# Modem_Carrier.net
KiCad netlist of a schematic drawn in EasyEDA Pro
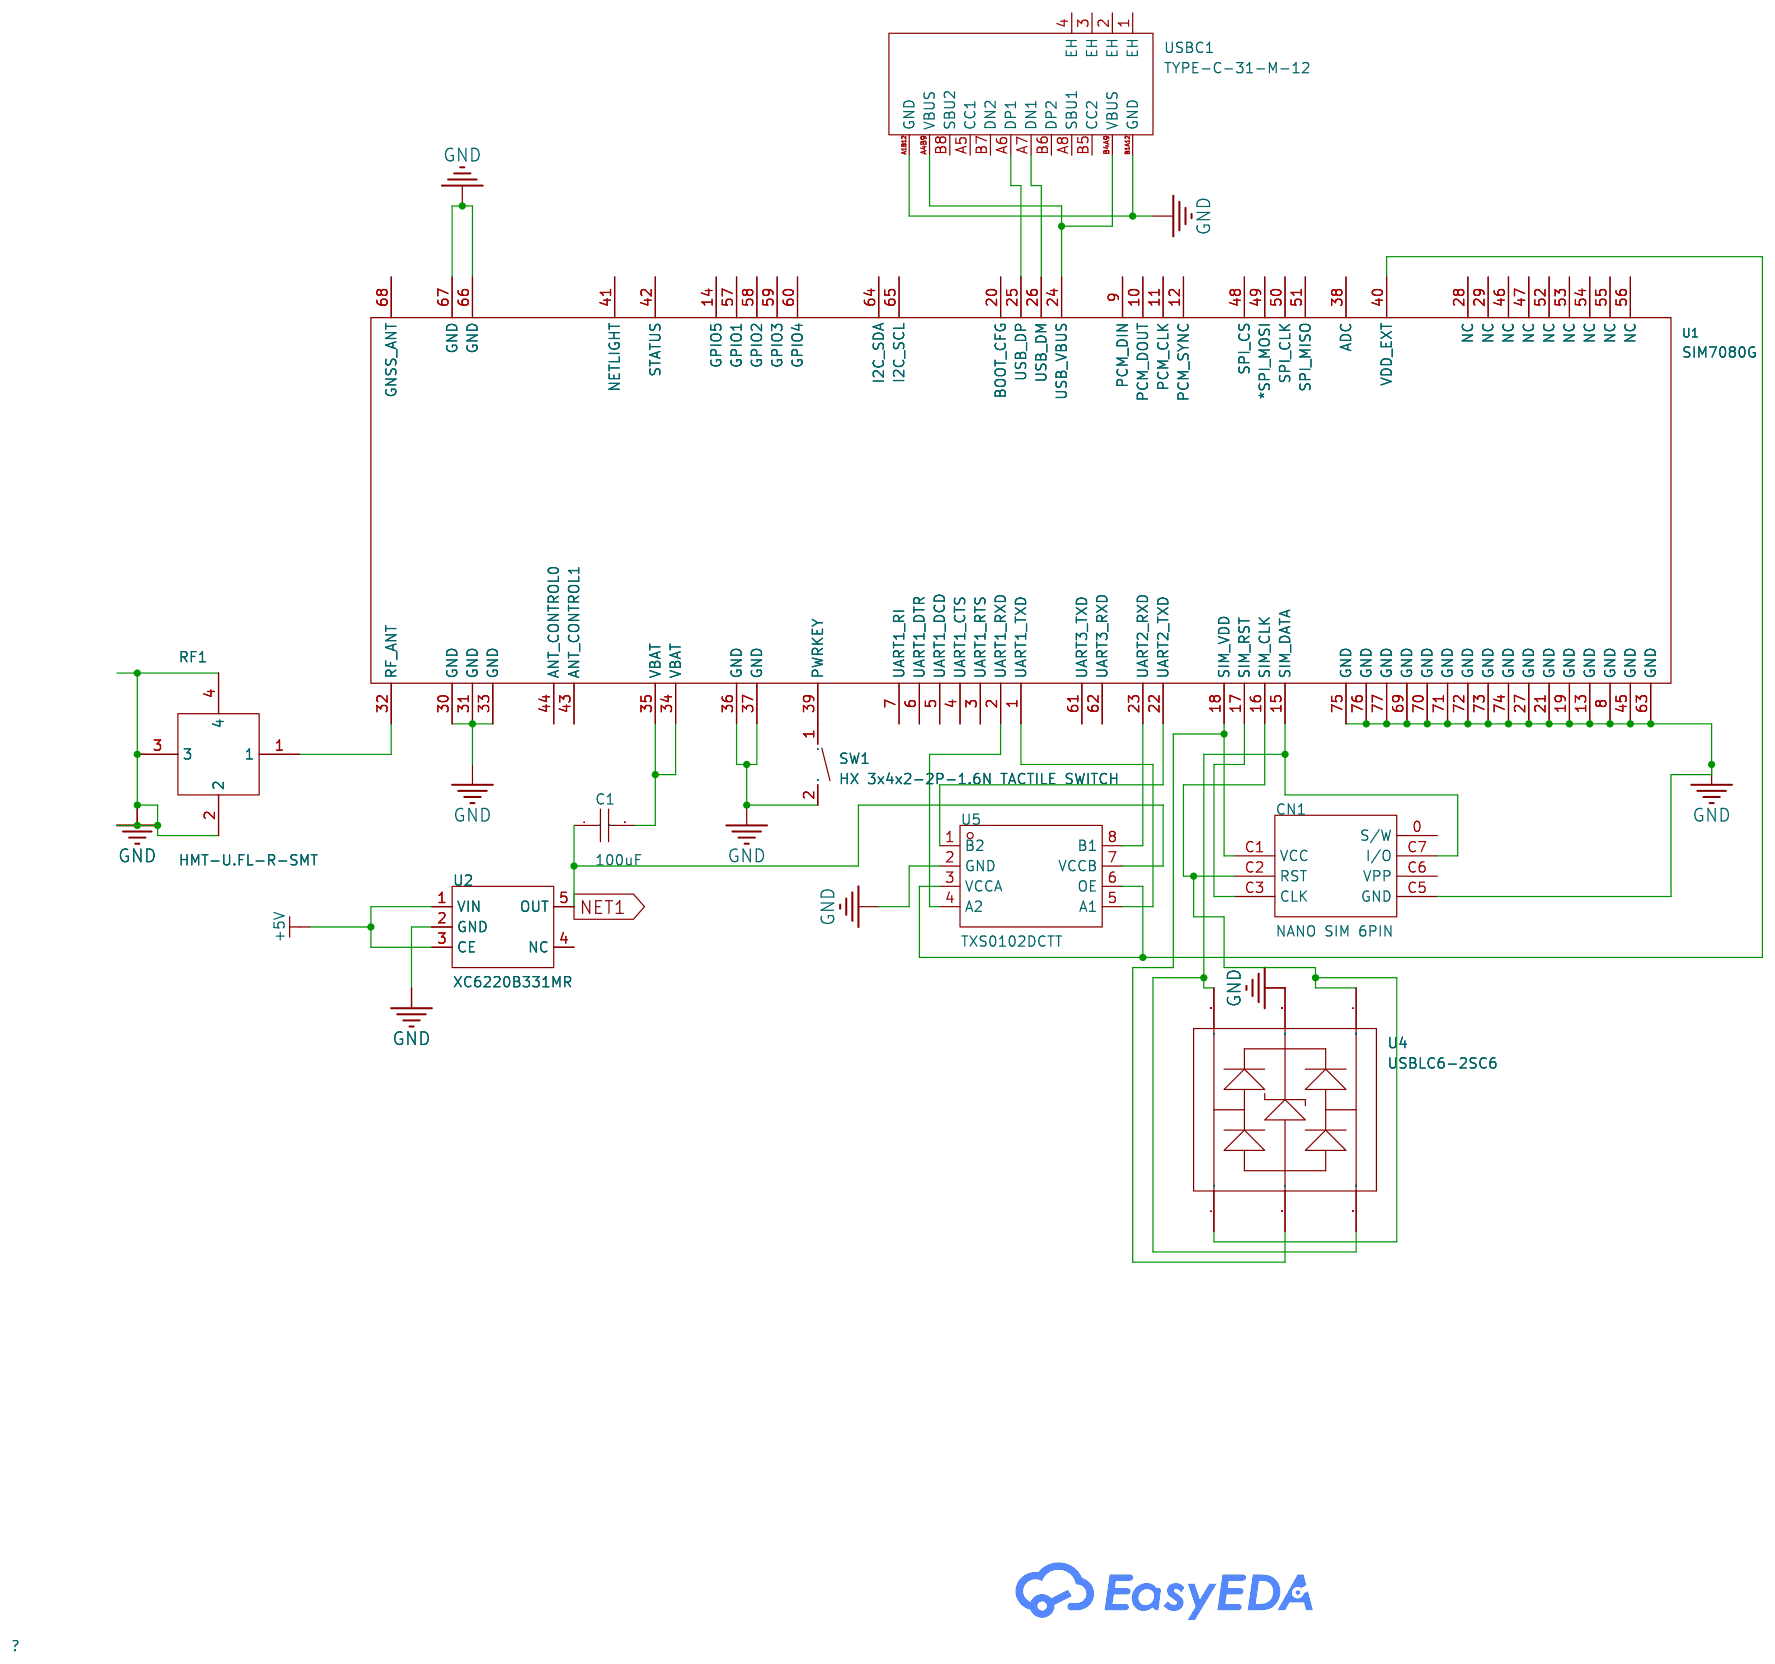
[diagram p0: schematic sheet]

(export (version "E")
  (design (tool "Eeschema 10.0.6"))
  (components
    (comp (ref "C1")
      (value "100uF")
      (footprint "easyedapro:C1206")
      (description "Capacitance:100uF Tolerance:±20% Tolerance:±20% Voltage Rating:6.3V Temperature Coefficient:X5R")
      (fields
        (field (name "Manufacturer Part") "CL31A107MQHNNNE")
        (field (name "Manufacturer") "SAMSUNG(三星)")
      )
      (libsource (lib "easyedapro") (part "CL31A107MQHNNNE"))
    )
    (comp (ref "CN1")
      (value "NANO SIM 6PIN")
      (footprint "easyedapro:SIM-SMD_C77877")
      (fields (field (name "Manufacturer") "BOOMELE(博穆精密)"))
      (libsource (lib "easyedapro") (part "nano1.4_c77877"))
    )
    (comp (ref "RF1")
      (value "HMT-U.FL-R-SMT")
      (footprint "easyedapro:IPEX-SMD_4P-L2.6-W2.6-LS3.1")
      (fields (field (name "Manufacturer") "HMTCONN(华明通)"))
      (libsource (lib "easyedapro") (part "HMT-U.FL-R-SMT"))
    )
    (comp (ref "SW1")
      (value "HX 3x4x2-2P-1.6N TACTILE SWITCH")
      (footprint "easyedapro:KEY-SMD_L4.0-W3.0-LS4.9-1")
      (fields (field (name "Manufacturer") "hanxia(韩下)"))
      (libsource (lib "easyedapro") (part "HX 3X4X2-2P-1.6N TACTILE SWITCH"))
    )
    (comp (ref "U1")
      (value "SIM7080G")
      (footprint "easyedapro:LCC-SMD_SIM7080G")
      (fields (field (name "Manufacturer") "SIMCOM(芯讯通无线科技)"))
      (libsource (lib "easyedapro") (part "SIM7080G"))
    )
    (comp (ref "U2")
      (value "XC6220B331MR")
      (footprint "easyedapro:SOT-23-5_L2.9-W1.6-P0.95-LS2.8-BR")
      (fields (field (name "Manufacturer") "TECH PUBLIC(台舟)"))
      (libsource (lib "easyedapro") (part "XC6220B331MR"))
    )
    (comp (ref "U4")
      (value "USBLC6-2SC6")
      (footprint "easyedapro:SOT-23-6_L2.9-W1.6-P0.95-LS2.8-BL")
      (fields (field (name "Manufacturer") "FUXINSEMI(富芯森美)"))
      (libsource (lib "easyedapro") (part "USBLC6-2SC6_C6807798"))
    )
    (comp (ref "U5")
      (value "TXS0102DCTT")
      (footprint "easyedapro:SSOP-8_L3.0-W2.8-P0.65-LS4.0-BL")
      (fields (field (name "Manufacturer") "TI(德州仪器)"))
      (libsource (lib "easyedapro") (part "TXS0102DCTT"))
    )
    (comp (ref "USBC1")
      (value "TYPE-C-31-M-12")
      (footprint "easyedapro:USB-C_SMD-TYPE-C-31-M-12_1")
      (fields (field (name "Manufacturer") "韩国韩荣"))
      (libsource (lib "easyedapro") (part "TYPE-C-31-M-12"))
    )
  )
  (nets
    (net (code "1") (name "+5V") (class "Default")
      (node (ref "U2") (pin "1") (pinfunction "VIN_1") (pintype "unspecified"))
      (node (ref "U2") (pin "3") (pinfunction "CE_3") (pintype "unspecified"))
    )
    (net (code "2") (name "GND") (class "Default")
      (node (ref "CN1") (pin "C5") (pinfunction "GND_C5") (pintype "unspecified"))
      (node (ref "RF1") (pin "2") (pinfunction "2_2") (pintype "unspecified"))
      (node (ref "RF1") (pin "3") (pinfunction "3_3") (pintype "unspecified"))
      (node (ref "RF1") (pin "4") (pinfunction "4_4") (pintype "unspecified"))
      (node (ref "SW1") (pin "2") (pinfunction "2_2") (pintype "unspecified"))
      (node (ref "U1") (pin "13") (pinfunction "GND_13") (pintype "input"))
      (node (ref "U1") (pin "19") (pinfunction "GND_19") (pintype "input"))
      (node (ref "U1") (pin "21") (pinfunction "GND_21") (pintype "input"))
      (node (ref "U1") (pin "27") (pinfunction "GND_27") (pintype "input"))
      (node (ref "U1") (pin "30") (pinfunction "GND_30") (pintype "input"))
      (node (ref "U1") (pin "31") (pinfunction "GND_31") (pintype "input"))
      (node (ref "U1") (pin "33") (pinfunction "GND_33") (pintype "input"))
      (node (ref "U1") (pin "36") (pinfunction "GND_36") (pintype "input"))
      (node (ref "U1") (pin "37") (pinfunction "GND_37") (pintype "input"))
      (node (ref "U1") (pin "45") (pinfunction "GND_45") (pintype "input"))
      (node (ref "U1") (pin "63") (pinfunction "GND_63") (pintype "input"))
      (node (ref "U1") (pin "66") (pinfunction "GND_66") (pintype "input"))
      (node (ref "U1") (pin "67") (pinfunction "GND_67") (pintype "input"))
      (node (ref "U1") (pin "69") (pinfunction "GND_69") (pintype "input"))
      (node (ref "U1") (pin "70") (pinfunction "GND_70") (pintype "input"))
      (node (ref "U1") (pin "71") (pinfunction "GND_71") (pintype "input"))
      (node (ref "U1") (pin "72") (pinfunction "GND_72") (pintype "input"))
      (node (ref "U1") (pin "73") (pinfunction "GND_73") (pintype "input"))
      (node (ref "U1") (pin "74") (pinfunction "GND_74") (pintype "input"))
      (node (ref "U1") (pin "75") (pinfunction "GND_75") (pintype "input"))
      (node (ref "U1") (pin "76") (pinfunction "GND_76") (pintype "input"))
      (node (ref "U1") (pin "77") (pinfunction "GND_77") (pintype "input"))
      (node (ref "U1") (pin "8") (pinfunction "GND_8") (pintype "input"))
      (node (ref "U2") (pin "2") (pinfunction "GND_2") (pintype "unspecified"))
      (node (ref "U4") (pin "5") (pinfunction "VCC_5") (pintype "input"))
      (node (ref "U5") (pin "2") (pinfunction "GND_2") (pintype "unspecified"))
      (node (ref "USBC1") (pin "A1B12") (pinfunction "GND_A1B12") (pintype "unspecified"))
      (node (ref "USBC1") (pin "B1A12") (pinfunction "GND_B1A12") (pintype "unspecified"))
    )
    (net (code "3") (name "NET1") (class "Default")
      (node (ref "C1") (pin "1") (pinfunction "1_1") (pintype "input"))
      (node (ref "U2") (pin "5") (pinfunction "OUT_5") (pintype "unspecified"))
      (node (ref "U5") (pin "7") (pinfunction "VCCB_7") (pintype "unspecified"))
    )
    (net (code "4") (name "Net-(C1-Pad2)") (class "Default")
      (node (ref "C1") (pin "2") (pinfunction "2_2") (pintype "input"))
      (node (ref "U1") (pin "34") (pinfunction "VBAT_34") (pintype "input"))
      (node (ref "U1") (pin "35") (pinfunction "VBAT_35") (pintype "input"))
    )
    (net (code "5") (name "Net-(CN1-CLK)") (class "Default")
      (node (ref "CN1") (pin "C3") (pinfunction "CLK_C3") (pintype "unspecified"))
      (node (ref "U1") (pin "17") (pinfunction "SIM_RST_17") (pintype "input"))
    )
    (net (code "6") (name "Net-(CN1-I{slash}O)") (class "Default")
      (node (ref "CN1") (pin "C7") (pinfunction "I/O_C7") (pintype "unspecified"))
      (node (ref "U1") (pin "15") (pinfunction "SIM_DATA_15") (pintype "input"))
      (node (ref "U4") (pin "3") (pinfunction "I/O2_3") (pintype "input"))
      (node (ref "U4") (pin "6") (pinfunction "I/O1_6") (pintype "input"))
    )
    (net (code "7") (name "Net-(CN1-RST)") (class "Default")
      (node (ref "CN1") (pin "C2") (pinfunction "RST_C2") (pintype "unspecified"))
      (node (ref "U1") (pin "16") (pinfunction "SIM_CLK_16") (pintype "input"))
      (node (ref "U4") (pin "1") (pinfunction "I/O1_1") (pintype "input"))
      (node (ref "U4") (pin "4") (pinfunction "I/O2_4") (pintype "input"))
    )
    (net (code "8") (name "Net-(CN1-VCC)") (class "Default")
      (node (ref "CN1") (pin "C1") (pinfunction "VCC_C1") (pintype "unspecified"))
      (node (ref "U1") (pin "18") (pinfunction "SIM_VDD_18") (pintype "input"))
      (node (ref "U4") (pin "2") (pinfunction "GND_2") (pintype "input"))
    )
    (net (code "9") (name "Net-(U1-PWRKEY)") (class "Default")
      (node (ref "SW1") (pin "1") (pinfunction "1_1") (pintype "unspecified"))
      (node (ref "U1") (pin "39") (pinfunction "PWRKEY_39") (pintype "input"))
    )
    (net (code "10") (name "Net-(U1-RF_ANT)") (class "Default")
      (node (ref "RF1") (pin "1") (pinfunction "1_1") (pintype "unspecified"))
      (node (ref "U1") (pin "32") (pinfunction "RF_ANT_32") (pintype "input"))
    )
    (net (code "11") (name "Net-(U1-UART1_RXD)") (class "Default")
      (node (ref "U1") (pin "2") (pinfunction "UART1_RXD_2") (pintype "input"))
      (node (ref "U5") (pin "4") (pinfunction "A2_4") (pintype "unspecified"))
    )
    (net (code "12") (name "Net-(U1-UART1_TXD)") (class "Default")
      (node (ref "U1") (pin "1") (pinfunction "UART1_TXD_1") (pintype "input"))
      (node (ref "U5") (pin "5") (pinfunction "A1_5") (pintype "unspecified"))
    )
    (net (code "13") (name "Net-(U1-UART2_RXD)") (class "Default")
      (node (ref "U1") (pin "23") (pinfunction "UART2_RXD_23") (pintype "input"))
      (node (ref "U5") (pin "8") (pinfunction "B1_8") (pintype "unspecified"))
    )
    (net (code "14") (name "Net-(U1-UART2_TXD)") (class "Default")
      (node (ref "U1") (pin "22") (pinfunction "UART2_TXD_22") (pintype "input"))
      (node (ref "U5") (pin "1") (pinfunction "B2_1") (pintype "unspecified"))
    )
    (net (code "15") (name "Net-(U1-USB_DM)") (class "Default")
      (node (ref "U1") (pin "26") (pinfunction "USB_DM_26") (pintype "input"))
      (node (ref "USBC1") (pin "A7") (pinfunction "DN1_A7") (pintype "unspecified"))
    )
    (net (code "16") (name "Net-(U1-USB_DP)") (class "Default")
      (node (ref "U1") (pin "25") (pinfunction "USB_DP_25") (pintype "input"))
      (node (ref "USBC1") (pin "A6") (pinfunction "DP1_A6") (pintype "unspecified"))
    )
    (net (code "17") (name "Net-(U1-USB_VBUS)") (class "Default")
      (node (ref "U1") (pin "24") (pinfunction "USB_VBUS_24") (pintype "input"))
      (node (ref "USBC1") (pin "A4B9") (pinfunction "VBUS_A4B9") (pintype "unspecified"))
      (node (ref "USBC1") (pin "B4A9") (pinfunction "VBUS_B4A9") (pintype "unspecified"))
    )
    (net (code "18") (name "Net-(U1-VDD_EXT)") (class "Default")
      (node (ref "U1") (pin "40") (pinfunction "VDD_EXT_40") (pintype "input"))
      (node (ref "U5") (pin "3") (pinfunction "VCCA_3") (pintype "unspecified"))
      (node (ref "U5") (pin "6") (pinfunction "OE_6") (pintype "unspecified"))
    )
    (net (code "19") (name "unconnected-(CN1-S{slash}W-Pad0)") (class "Default")
      (node (ref "CN1") (pin "0") (pinfunction "S/W_0") (pintype "unspecified"))
    )
    (net (code "20") (name "unconnected-(CN1-VPP-PadC6)") (class "Default")
      (node (ref "CN1") (pin "C6") (pinfunction "VPP_C6") (pintype "unspecified"))
    )
    (net (code "21") (name "unconnected-(U1-*SPI_MOSI-Pad49)") (class "Default")
      (node (ref "U1") (pin "49") (pinfunction "*SPI_MOSI_49") (pintype "input"))
    )
    (net (code "22") (name "unconnected-(U1-ADC-Pad38)") (class "Default")
      (node (ref "U1") (pin "38") (pinfunction "ADC_38") (pintype "input"))
    )
    (net (code "23") (name "unconnected-(U1-ANT_CONTROL0-Pad44)") (class "Default")
      (node (ref "U1") (pin "44") (pinfunction "ANT_CONTROL0_44") (pintype "input"))
    )
    (net (code "24") (name "unconnected-(U1-ANT_CONTROL1-Pad43)") (class "Default")
      (node (ref "U1") (pin "43") (pinfunction "ANT_CONTROL1_43") (pintype "input"))
    )
    (net (code "25") (name "unconnected-(U1-BOOT_CFG-Pad20)") (class "Default")
      (node (ref "U1") (pin "20") (pinfunction "BOOT_CFG_20") (pintype "input"))
    )
    (net (code "26") (name "unconnected-(U1-GNSS_ANT-Pad68)") (class "Default")
      (node (ref "U1") (pin "68") (pinfunction "GNSS_ANT_68") (pintype "input"))
    )
    (net (code "27") (name "unconnected-(U1-GPIO1-Pad57)") (class "Default")
      (node (ref "U1") (pin "57") (pinfunction "GPIO1_57") (pintype "input"))
    )
    (net (code "28") (name "unconnected-(U1-GPIO2-Pad58)") (class "Default")
      (node (ref "U1") (pin "58") (pinfunction "GPIO2_58") (pintype "input"))
    )
    (net (code "29") (name "unconnected-(U1-GPIO3-Pad59)") (class "Default")
      (node (ref "U1") (pin "59") (pinfunction "GPIO3_59") (pintype "input"))
    )
    (net (code "30") (name "unconnected-(U1-GPIO4-Pad60)") (class "Default")
      (node (ref "U1") (pin "60") (pinfunction "GPIO4_60") (pintype "input"))
    )
    (net (code "31") (name "unconnected-(U1-GPIO5-Pad14)") (class "Default")
      (node (ref "U1") (pin "14") (pinfunction "GPIO5_14") (pintype "input"))
    )
    (net (code "32") (name "unconnected-(U1-I2C_SCL-Pad65)") (class "Default")
      (node (ref "U1") (pin "65") (pinfunction "I2C_SCL_65") (pintype "input"))
    )
    (net (code "33") (name "unconnected-(U1-I2C_SDA-Pad64)") (class "Default")
      (node (ref "U1") (pin "64") (pinfunction "I2C_SDA_64") (pintype "input"))
    )
    (net (code "34") (name "unconnected-(U1-NC-Pad28)") (class "Default")
      (node (ref "U1") (pin "28") (pinfunction "NC_28") (pintype "input"))
    )
    (net (code "35") (name "unconnected-(U1-NC-Pad29)") (class "Default")
      (node (ref "U1") (pin "29") (pinfunction "NC_29") (pintype "input"))
    )
    (net (code "36") (name "unconnected-(U1-NC-Pad46)") (class "Default")
      (node (ref "U1") (pin "46") (pinfunction "NC_46") (pintype "input"))
    )
    (net (code "37") (name "unconnected-(U1-NC-Pad47)") (class "Default")
      (node (ref "U1") (pin "47") (pinfunction "NC_47") (pintype "input"))
    )
    (net (code "38") (name "unconnected-(U1-NC-Pad52)") (class "Default")
      (node (ref "U1") (pin "52") (pinfunction "NC_52") (pintype "input"))
    )
    (net (code "39") (name "unconnected-(U1-NC-Pad53)") (class "Default")
      (node (ref "U1") (pin "53") (pinfunction "NC_53") (pintype "input"))
    )
    (net (code "40") (name "unconnected-(U1-NC-Pad54)") (class "Default")
      (node (ref "U1") (pin "54") (pinfunction "NC_54") (pintype "input"))
    )
    (net (code "41") (name "unconnected-(U1-NC-Pad55)") (class "Default")
      (node (ref "U1") (pin "55") (pinfunction "NC_55") (pintype "input"))
    )
    (net (code "42") (name "unconnected-(U1-NC-Pad56)") (class "Default")
      (node (ref "U1") (pin "56") (pinfunction "NC_56") (pintype "input"))
    )
    (net (code "43") (name "unconnected-(U1-NETLIGHT-Pad41)") (class "Default")
      (node (ref "U1") (pin "41") (pinfunction "NETLIGHT_41") (pintype "input"))
    )
    (net (code "44") (name "unconnected-(U1-PCM_CLK-Pad11)") (class "Default")
      (node (ref "U1") (pin "11") (pinfunction "PCM_CLK_11") (pintype "input"))
    )
    (net (code "45") (name "unconnected-(U1-PCM_DIN-Pad9)") (class "Default")
      (node (ref "U1") (pin "9") (pinfunction "PCM_DIN_9") (pintype "input"))
    )
    (net (code "46") (name "unconnected-(U1-PCM_DOUT-Pad10)") (class "Default")
      (node (ref "U1") (pin "10") (pinfunction "PCM_DOUT_10") (pintype "input"))
    )
    (net (code "47") (name "unconnected-(U1-PCM_SYNC-Pad12)") (class "Default")
      (node (ref "U1") (pin "12") (pinfunction "PCM_SYNC_12") (pintype "input"))
    )
    (net (code "48") (name "unconnected-(U1-SPI_CLK-Pad50)") (class "Default")
      (node (ref "U1") (pin "50") (pinfunction "SPI_CLK_50") (pintype "input"))
    )
    (net (code "49") (name "unconnected-(U1-SPI_CS-Pad48)") (class "Default")
      (node (ref "U1") (pin "48") (pinfunction "SPI_CS_48") (pintype "input"))
    )
    (net (code "50") (name "unconnected-(U1-SPI_MISO-Pad51)") (class "Default")
      (node (ref "U1") (pin "51") (pinfunction "SPI_MISO_51") (pintype "input"))
    )
    (net (code "51") (name "unconnected-(U1-STATUS-Pad42)") (class "Default")
      (node (ref "U1") (pin "42") (pinfunction "STATUS_42") (pintype "input"))
    )
    (net (code "52") (name "unconnected-(U1-UART1_CTS-Pad4)") (class "Default")
      (node (ref "U1") (pin "4") (pinfunction "UART1_CTS_4") (pintype "input"))
    )
    (net (code "53") (name "unconnected-(U1-UART1_DCD-Pad5)") (class "Default")
      (node (ref "U1") (pin "5") (pinfunction "UART1_DCD_5") (pintype "input"))
    )
    (net (code "54") (name "unconnected-(U1-UART1_DTR-Pad6)") (class "Default")
      (node (ref "U1") (pin "6") (pinfunction "UART1_DTR_6") (pintype "input"))
    )
    (net (code "55") (name "unconnected-(U1-UART1_RI-Pad7)") (class "Default")
      (node (ref "U1") (pin "7") (pinfunction "UART1_RI_7") (pintype "input"))
    )
    (net (code "56") (name "unconnected-(U1-UART1_RTS-Pad3)") (class "Default")
      (node (ref "U1") (pin "3") (pinfunction "UART1_RTS_3") (pintype "input"))
    )
    (net (code "57") (name "unconnected-(U1-UART3_RXD-Pad62)") (class "Default")
      (node (ref "U1") (pin "62") (pinfunction "UART3_RXD_62") (pintype "input"))
    )
    (net (code "58") (name "unconnected-(U1-UART3_TXD-Pad61)") (class "Default")
      (node (ref "U1") (pin "61") (pinfunction "UART3_TXD_61") (pintype "input"))
    )
    (net (code "59") (name "unconnected-(U2-NC-Pad4)") (class "Default")
      (node (ref "U2") (pin "4") (pinfunction "NC_4") (pintype "unspecified"))
    )
    (net (code "60") (name "unconnected-(USBC1-CC1-PadA5)") (class "Default")
      (node (ref "USBC1") (pin "A5") (pinfunction "CC1_A5") (pintype "unspecified"))
    )
    (net (code "61") (name "unconnected-(USBC1-CC2-PadB5)") (class "Default")
      (node (ref "USBC1") (pin "B5") (pinfunction "CC2_B5") (pintype "unspecified"))
    )
    (net (code "62") (name "unconnected-(USBC1-DN2-PadB7)") (class "Default")
      (node (ref "USBC1") (pin "B7") (pinfunction "DN2_B7") (pintype "unspecified"))
    )
    (net (code "63") (name "unconnected-(USBC1-DP2-PadB6)") (class "Default")
      (node (ref "USBC1") (pin "B6") (pinfunction "DP2_B6") (pintype "unspecified"))
    )
    (net (code "64") (name "unconnected-(USBC1-EH-Pad1)") (class "Default")
      (node (ref "USBC1") (pin "1") (pinfunction "EH_1") (pintype "unspecified"))
    )
    (net (code "65") (name "unconnected-(USBC1-EH-Pad2)") (class "Default")
      (node (ref "USBC1") (pin "2") (pinfunction "EH_2") (pintype "unspecified"))
    )
    (net (code "66") (name "unconnected-(USBC1-EH-Pad3)") (class "Default")
      (node (ref "USBC1") (pin "3") (pinfunction "EH_3") (pintype "unspecified"))
    )
    (net (code "67") (name "unconnected-(USBC1-EH-Pad4)") (class "Default")
      (node (ref "USBC1") (pin "4") (pinfunction "EH_4") (pintype "unspecified"))
    )
    (net (code "68") (name "unconnected-(USBC1-SBU1-PadA8)") (class "Default")
      (node (ref "USBC1") (pin "A8") (pinfunction "SBU1_A8") (pintype "unspecified"))
    )
    (net (code "69") (name "unconnected-(USBC1-SBU2-PadB8)") (class "Default")
      (node (ref "USBC1") (pin "B8") (pinfunction "SBU2_B8") (pintype "unspecified"))
    )
  )
)
